# 14_-CURRENT_METER.net
KiCad netlist of a schematic drawn in Altium Designer
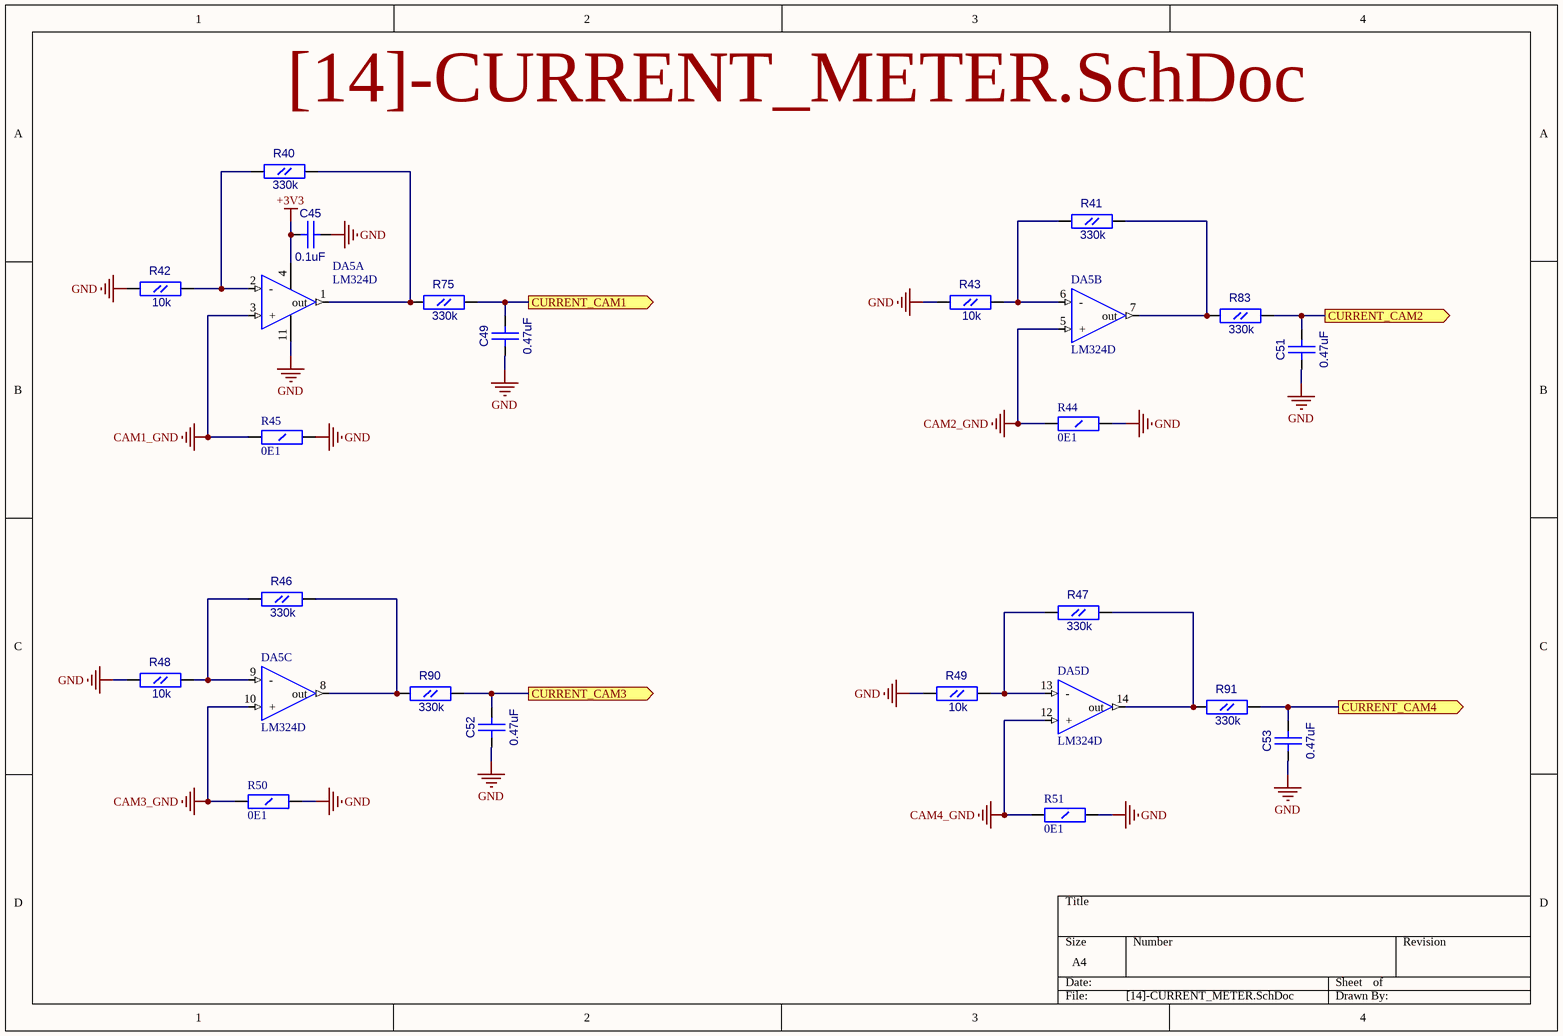
[diagram p0: [14]-CURRENT_METER.SchDoc]

(export (version "E")
  (design (tool "Eeschema 10.0.6"))
  (components
    (comp (ref "C45")
      (value "0.1uF")
      (footprint "CC0603")
      (description "CC0603")
      (libsource (lib "fizik_lib") (part "CC0603"))
    )
    (comp (ref "C49")
      (value "0.47uF")
      (footprint "CC0603")
      (description "CC0603")
      (libsource (lib "fizik_lib") (part "CC0603"))
    )
    (comp (ref "C51")
      (value "0.47uF")
      (footprint "CC0603")
      (description "CC0603")
      (libsource (lib "fizik_lib") (part "CC0603"))
    )
    (comp (ref "C52")
      (value "0.47uF")
      (footprint "CC0603")
      (description "CC0603")
      (libsource (lib "fizik_lib") (part "CC0603"))
    )
    (comp (ref "C53")
      (value "0.47uF")
      (footprint "CC0603")
      (description "CC0603")
      (libsource (lib "fizik_lib") (part "CC0603"))
    )
    (comp (ref "DA5") (value "LM324D") (footprint "SO14") (libsource (lib "fizik_lib") (part "LM324D")))
    (comp (ref "R40")
      (value "330k")
      (footprint "RC0603")
      (description "RC0603")
      (libsource (lib "fizik_lib") (part "RC0603"))
    )
    (comp (ref "R41")
      (value "330k")
      (footprint "RC0603")
      (description "RC0603")
      (libsource (lib "fizik_lib") (part "RC0603"))
    )
    (comp (ref "R42")
      (value "10k")
      (footprint "RC0603")
      (description "RC0603")
      (libsource (lib "fizik_lib") (part "RC0603"))
    )
    (comp (ref "R43")
      (value "10k")
      (footprint "RC0603")
      (description "RC0603")
      (libsource (lib "fizik_lib") (part "RC0603"))
    )
    (comp (ref "R44")
      (value "0E1")
      (footprint "R2512")
      (description "Resistor 2512 1W")
      (libsource (lib "fizik_lib") (part "RC2512"))
    )
    (comp (ref "R45")
      (value "0E1")
      (footprint "R2512")
      (description "Resistor 2512 1W")
      (libsource (lib "fizik_lib") (part "RC2512"))
    )
    (comp (ref "R46")
      (value "330k")
      (footprint "RC0603")
      (description "RC0603")
      (libsource (lib "fizik_lib") (part "RC0603"))
    )
    (comp (ref "R47")
      (value "330k")
      (footprint "RC0603")
      (description "RC0603")
      (libsource (lib "fizik_lib") (part "RC0603"))
    )
    (comp (ref "R48")
      (value "10k")
      (footprint "RC0603")
      (description "RC0603")
      (libsource (lib "fizik_lib") (part "RC0603"))
    )
    (comp (ref "R49")
      (value "10k")
      (footprint "RC0603")
      (description "RC0603")
      (libsource (lib "fizik_lib") (part "RC0603"))
    )
    (comp (ref "R50")
      (value "0E1")
      (footprint "R2512")
      (description "Resistor 2512 1W")
      (libsource (lib "fizik_lib") (part "RC2512"))
    )
    (comp (ref "R51")
      (value "0E1")
      (footprint "R2512")
      (description "Resistor 2512 1W")
      (libsource (lib "fizik_lib") (part "RC2512"))
    )
    (comp (ref "R75")
      (value "330k")
      (footprint "RC0603")
      (description "RC0603")
      (libsource (lib "fizik_lib") (part "RC0603"))
    )
    (comp (ref "R83")
      (value "330k")
      (footprint "RC0603")
      (description "RC0603")
      (libsource (lib "fizik_lib") (part "RC0603"))
    )
    (comp (ref "R90")
      (value "330k")
      (footprint "RC0603")
      (description "RC0603")
      (libsource (lib "fizik_lib") (part "RC0603"))
    )
    (comp (ref "R91")
      (value "330k")
      (footprint "RC0603")
      (description "RC0603")
      (libsource (lib "fizik_lib") (part "RC0603"))
    )
  )
  (nets
    (net (code "1") (name "+3V3") (class "Default")
      (node (ref "C45") (pin "1") (pinfunction "A_1") (pintype "passive"))
      (node (ref "DA5") (pin "4") (pinfunction "V+_4") (pintype "passive"))
    )
    (net (code "2") (name "/CURRENT_CAM1") (class "Default")
      (node (ref "C49") (pin "2") (pinfunction "B_2") (pintype "passive"))
      (node (ref "R75") (pin "2") (pinfunction "B_2") (pintype "passive"))
    )
    (net (code "3") (name "/CURRENT_CAM2") (class "Default")
      (node (ref "C51") (pin "2") (pinfunction "B_2") (pintype "passive"))
      (node (ref "R83") (pin "2") (pinfunction "B_2") (pintype "passive"))
    )
    (net (code "4") (name "/CURRENT_CAM3") (class "Default")
      (node (ref "C52") (pin "2") (pinfunction "B_2") (pintype "passive"))
      (node (ref "R90") (pin "2") (pinfunction "B_2") (pintype "passive"))
    )
    (net (code "5") (name "/CURRENT_CAM4") (class "Default")
      (node (ref "C53") (pin "2") (pinfunction "B_2") (pintype "passive"))
      (node (ref "R91") (pin "2") (pinfunction "B_2") (pintype "passive"))
    )
    (net (code "6") (name "CAM1_GND") (class "Default")
      (node (ref "DA5") (pin "3") (pinfunction "+_3") (pintype "input"))
      (node (ref "R45") (pin "2") (pinfunction "B_2") (pintype "passive"))
    )
    (net (code "7") (name "CAM2_GND") (class "Default")
      (node (ref "DA5") (pin "5") (pinfunction "+_5") (pintype "input"))
      (node (ref "R44") (pin "2") (pinfunction "B_2") (pintype "passive"))
    )
    (net (code "8") (name "CAM3_GND") (class "Default")
      (node (ref "DA5") (pin "10") (pinfunction "+_10") (pintype "input"))
      (node (ref "R50") (pin "2") (pinfunction "B_2") (pintype "passive"))
    )
    (net (code "9") (name "CAM4_GND") (class "Default")
      (node (ref "DA5") (pin "12") (pinfunction "+_12") (pintype "input"))
      (node (ref "R51") (pin "2") (pinfunction "B_2") (pintype "passive"))
    )
    (net (code "10") (name "GND") (class "Default")
      (node (ref "C45") (pin "2") (pinfunction "B_2") (pintype "passive"))
      (node (ref "C49") (pin "1") (pinfunction "A_1") (pintype "passive"))
      (node (ref "C51") (pin "1") (pinfunction "A_1") (pintype "passive"))
      (node (ref "C52") (pin "1") (pinfunction "A_1") (pintype "passive"))
      (node (ref "C53") (pin "1") (pinfunction "A_1") (pintype "passive"))
      (node (ref "DA5") (pin "11") (pinfunction "V-_11") (pintype "passive"))
      (node (ref "R42") (pin "1") (pinfunction "A_1") (pintype "passive"))
      (node (ref "R43") (pin "1") (pinfunction "A_1") (pintype "passive"))
      (node (ref "R44") (pin "1") (pinfunction "A_1") (pintype "passive"))
      (node (ref "R45") (pin "1") (pinfunction "A_1") (pintype "passive"))
      (node (ref "R48") (pin "1") (pinfunction "A_1") (pintype "passive"))
      (node (ref "R49") (pin "1") (pinfunction "A_1") (pintype "passive"))
      (node (ref "R50") (pin "1") (pinfunction "A_1") (pintype "passive"))
      (node (ref "R51") (pin "1") (pinfunction "A_1") (pintype "passive"))
    )
    (net (code "11") (name "Net-(DA5A--)") (class "Default")
      (node (ref "DA5") (pin "2") (pinfunction "-_2") (pintype "input"))
      (node (ref "R40") (pin "1") (pinfunction "A_1") (pintype "passive"))
      (node (ref "R42") (pin "2") (pinfunction "B_2") (pintype "passive"))
    )
    (net (code "12") (name "Net-(DA5A-out)") (class "Default")
      (node (ref "DA5") (pin "1") (pinfunction "out_1") (pintype "output"))
      (node (ref "R40") (pin "2") (pinfunction "B_2") (pintype "passive"))
      (node (ref "R75") (pin "1") (pinfunction "A_1") (pintype "passive"))
    )
    (net (code "13") (name "Net-(DA5B--)") (class "Default")
      (node (ref "DA5") (pin "6") (pinfunction "-_6") (pintype "input"))
      (node (ref "R41") (pin "1") (pinfunction "A_1") (pintype "passive"))
      (node (ref "R43") (pin "2") (pinfunction "B_2") (pintype "passive"))
    )
    (net (code "14") (name "Net-(DA5B-out)") (class "Default")
      (node (ref "DA5") (pin "7") (pinfunction "out_7") (pintype "output"))
      (node (ref "R41") (pin "2") (pinfunction "B_2") (pintype "passive"))
      (node (ref "R83") (pin "1") (pinfunction "A_1") (pintype "passive"))
    )
    (net (code "15") (name "Net-(DA5C--)") (class "Default")
      (node (ref "DA5") (pin "9") (pinfunction "-_9") (pintype "input"))
      (node (ref "R46") (pin "1") (pinfunction "A_1") (pintype "passive"))
      (node (ref "R48") (pin "2") (pinfunction "B_2") (pintype "passive"))
    )
    (net (code "16") (name "Net-(DA5C-out)") (class "Default")
      (node (ref "DA5") (pin "8") (pinfunction "out_8") (pintype "output"))
      (node (ref "R46") (pin "2") (pinfunction "B_2") (pintype "passive"))
      (node (ref "R90") (pin "1") (pinfunction "A_1") (pintype "passive"))
    )
    (net (code "17") (name "Net-(DA5D--)") (class "Default")
      (node (ref "DA5") (pin "13") (pinfunction "-_13") (pintype "input"))
      (node (ref "R47") (pin "1") (pinfunction "A_1") (pintype "passive"))
      (node (ref "R49") (pin "2") (pinfunction "B_2") (pintype "passive"))
    )
    (net (code "18") (name "Net-(DA5D-out)") (class "Default")
      (node (ref "DA5") (pin "14") (pinfunction "out_14") (pintype "output"))
      (node (ref "R47") (pin "2") (pinfunction "B_2") (pintype "passive"))
      (node (ref "R91") (pin "1") (pinfunction "A_1") (pintype "passive"))
    )
  )
)
